# tritiled_nocell_rprogrammable.net
KiCad netlist of a schematic drawn in EAGLE
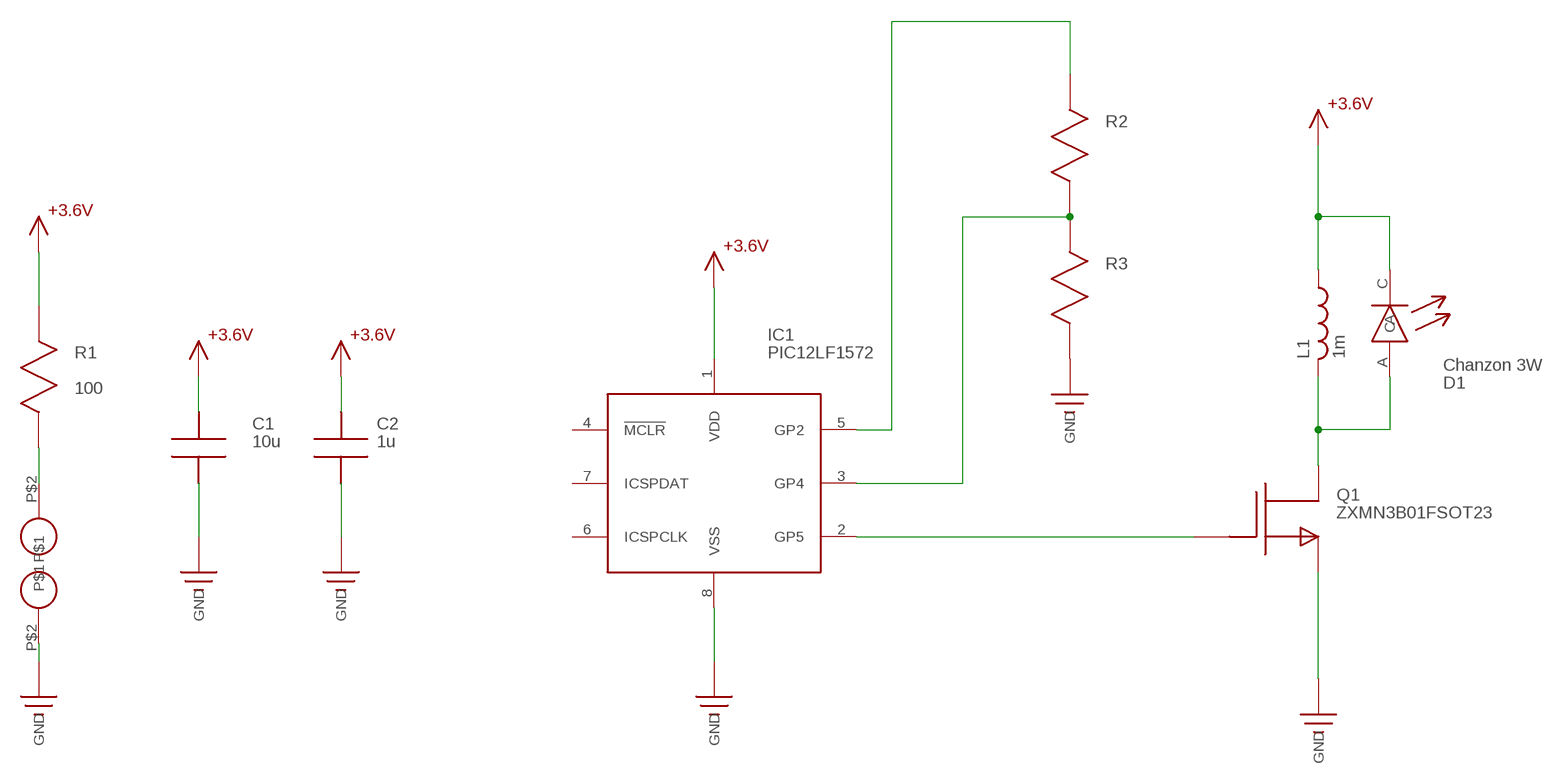
[diagram p0: schematic, sheet 1]

(export (version "E")
  (design (tool "Eeschema 10.0.6"))
  (components
    (comp (ref "C1")
      (value "10u")
      (footprint "eagle-import:1206")
      (libsource (lib "eagle-import") (part "C1206"))
    )
    (comp (ref "C2")
      (value "1u")
      (footprint "eagle-import:C0603")
      (libsource (lib "eagle-import") (part "C0603"))
    )
    (comp (ref "D1")
      (value "Chanzon 3W")
      (footprint "eagle-import:LED_3W")
      (libsource (lib "eagle-import") (part "LED_3W"))
    )
    (comp (ref "IC1")
      (value "PIC12LF1572")
      (footprint "eagle-import:SOIC8")
      (libsource (lib "eagle-import") (part "PIC12LF1571"))
    )
    (comp (ref "L1")
      (value "1m")
      (footprint "eagle-import:SRR6028_INDUCTOR")
      (libsource (lib "eagle-import") (part "SRR6028_INDUCTOR"))
    )
    (comp (ref "Q1")
      (value "ZXMN3B01FSOT23")
      (footprint "eagle-import:SOT-23")
      (libsource (lib "eagle-import") (part "ZXMN3B01FSOT23"))
    )
    (comp (ref "R1")
      (value "100")
      (footprint "eagle-import:R1206")
      (libsource (lib "eagle-import") (part "R1206"))
    )
    (comp (ref "R2")
      (value "R1206")
      (footprint "eagle-import:R1206")
      (libsource (lib "eagle-import") (part "R1206"))
    )
    (comp (ref "R3")
      (value "R1206")
      (footprint "eagle-import:R1206")
      (libsource (lib "eagle-import") (part "R1206"))
    )
    (comp (ref "U$7")
      (value "ICSP_PAD")
      (footprint "eagle-import:ICSP_PAD")
      (libsource (lib "eagle-import") (part "ICSP_PAD"))
    )
    (comp (ref "U$9")
      (value "ICSP_PAD")
      (footprint "eagle-import:ICSP_PAD")
      (libsource (lib "eagle-import") (part "ICSP_PAD"))
    )
  )
  (nets
    (net (code "1") (name "+3.6V") (class "Default")
      (node (ref "C1") (pin "P$1") (pinfunction "P$1_P$1") (pintype "bidirectional"))
      (node (ref "C2") (pin "P$1") (pinfunction "P$1_P$1") (pintype "bidirectional"))
      (node (ref "D1") (pin "C") (pinfunction "C_C") (pintype "bidirectional"))
      (node (ref "IC1") (pin "1") (pinfunction "VDD_1") (pintype "bidirectional"))
      (node (ref "L1") (pin "P$1") (pinfunction "1_P$1") (pintype "passive"))
      (node (ref "R1") (pin "P$1") (pinfunction "P$1_P$1") (pintype "bidirectional"))
    )
    (net (code "2") (name "GND") (class "Default")
      (node (ref "C1") (pin "P$2") (pinfunction "P$2_P$2") (pintype "bidirectional"))
      (node (ref "C2") (pin "P$2") (pinfunction "P$2_P$2") (pintype "bidirectional"))
      (node (ref "IC1") (pin "8") (pinfunction "VSS_8") (pintype "bidirectional"))
      (node (ref "Q1") (pin "2") (pinfunction "S_2") (pintype "bidirectional"))
      (node (ref "R3") (pin "P$2") (pinfunction "P$2_P$2") (pintype "bidirectional"))
      (node (ref "U$9") (pin "P$2") (pinfunction "P$1_P$2") (pintype "bidirectional"))
    )
    (net (code "3") (name "Net-(IC1-GP2)") (class "Default")
      (node (ref "IC1") (pin "5") (pinfunction "GP2_5") (pintype "bidirectional"))
      (node (ref "R2") (pin "P$1") (pinfunction "P$1_P$1") (pintype "bidirectional"))
    )
    (net (code "4") (name "Net-(IC1-GP4)") (class "Default")
      (node (ref "IC1") (pin "3") (pinfunction "GP4_3") (pintype "bidirectional"))
      (node (ref "R2") (pin "P$2") (pinfunction "P$2_P$2") (pintype "bidirectional"))
      (node (ref "R3") (pin "P$1") (pinfunction "P$1_P$1") (pintype "bidirectional"))
    )
    (net (code "5") (name "Net-(IC1-GP5)") (class "Default")
      (node (ref "IC1") (pin "2") (pinfunction "GP5_2") (pintype "bidirectional"))
      (node (ref "Q1") (pin "1") (pinfunction "G_1") (pintype "bidirectional"))
    )
    (net (code "6") (name "Net-(L1-2)") (class "Default")
      (node (ref "D1") (pin "A") (pinfunction "A_A") (pintype "bidirectional"))
      (node (ref "L1") (pin "P$2") (pinfunction "2_P$2") (pintype "passive"))
      (node (ref "Q1") (pin "3") (pinfunction "D_3") (pintype "bidirectional"))
    )
    (net (code "7") (name "Net-(U$7-P$1)") (class "Default")
      (node (ref "R1") (pin "P$2") (pinfunction "P$2_P$2") (pintype "bidirectional"))
      (node (ref "U$7") (pin "P$2") (pinfunction "P$1_P$2") (pintype "bidirectional"))
    )
    (net (code "8") (name "unconnected-(IC1-ICSPCLK-Pad6)") (class "Default")
      (node (ref "IC1") (pin "6") (pinfunction "ICSPCLK_6") (pintype "bidirectional"))
    )
    (net (code "9") (name "unconnected-(IC1-ICSPDAT-Pad7)") (class "Default")
      (node (ref "IC1") (pin "7") (pinfunction "ICSPDAT_7") (pintype "bidirectional"))
    )
    (net (code "10") (name "unconnected-(IC1-~{MCLR}-Pad4)") (class "Default")
      (node (ref "IC1") (pin "4") (pinfunction "~{MCLR}_4") (pintype "bidirectional"))
    )
  )
)
